# ic-tester.net
KiCad netlist of a schematic drawn in EAGLE
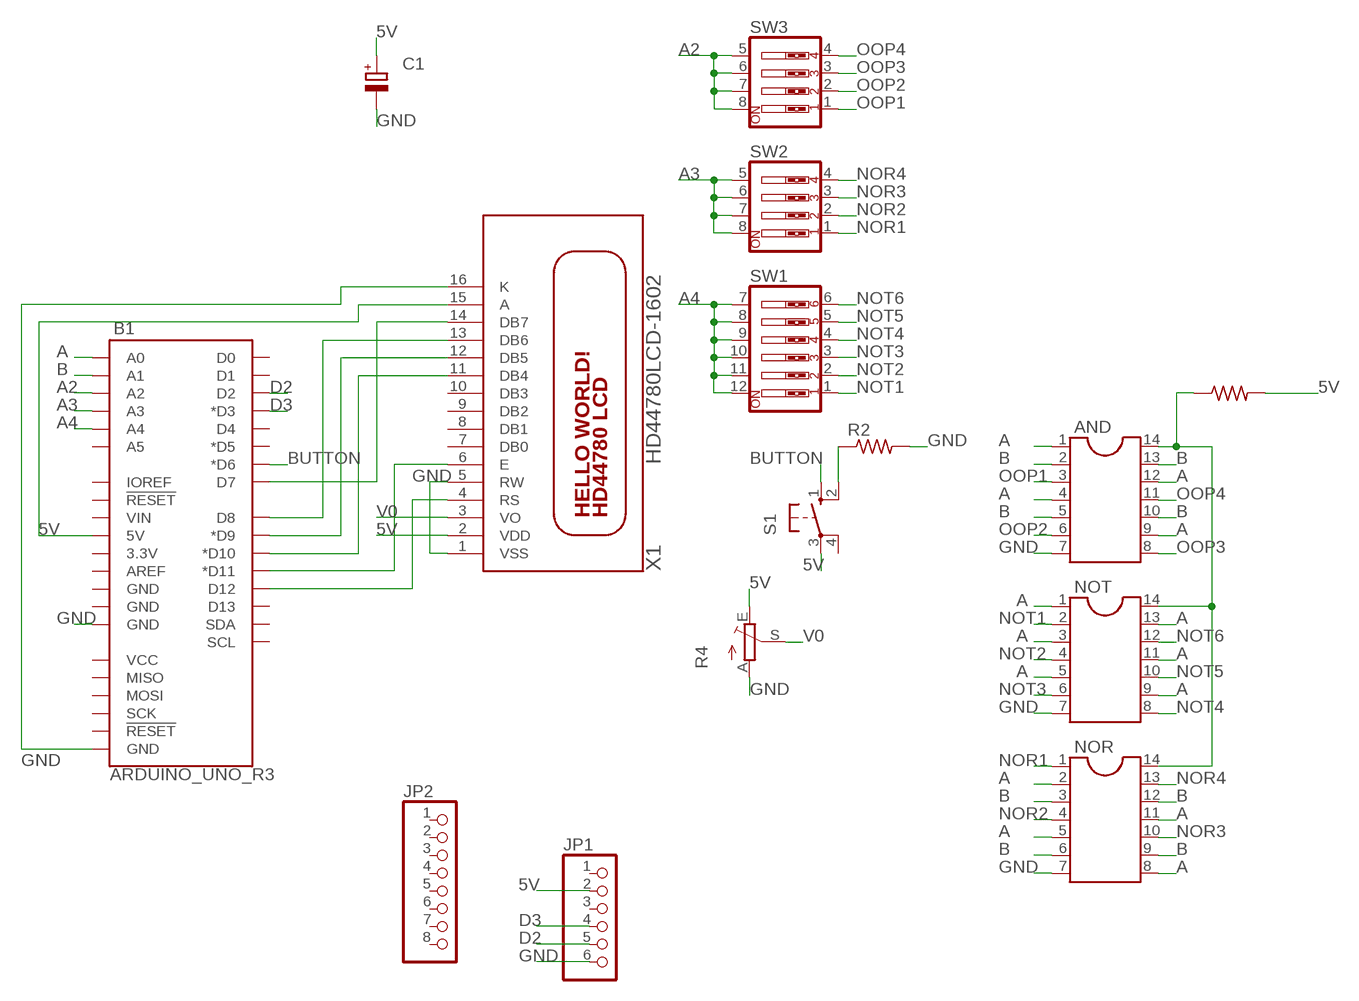
[diagram p0: schematic, sheet 1]

(export (version "E")
  (design (tool "Eeschema 10.0.6"))
  (components
    (comp (ref "AND")
      (value "DIL14")
      (footprint "eagle-import:DIL14")
      (libsource (lib "eagle-import") (part "DIL14"))
    )
    (comp (ref "B1")
      (value "ARDUINO_UNO_R3")
      (footprint "eagle-import:ARDUINO_R3")
      (libsource (lib "eagle-import") (part "ARDUINO_UNO_R3"))
    )
    (comp (ref "C1")
      (value "CPOL-EUE7.5-16")
      (footprint "eagle-import:E7,5-16")
      (libsource (lib "eagle-import") (part "CPOL-EUE7.5-16"))
    )
    (comp (ref "JP1")
      (value "PINHD-1X6")
      (footprint "eagle-import:1X06")
      (libsource (lib "eagle-import") (part "PINHD-1X6"))
    )
    (comp (ref "JP2")
      (value "PINHD-1X8BIG")
      (footprint "eagle-import:1X08-BIG")
      (libsource (lib "eagle-import") (part "PINHD-1X8BIG"))
    )
    (comp (ref "NOR")
      (value "DIL14")
      (footprint "eagle-import:DIL14")
      (libsource (lib "eagle-import") (part "DIL14"))
    )
    (comp (ref "NOT")
      (value "DIL14")
      (footprint "eagle-import:DIL14")
      (libsource (lib "eagle-import") (part "DIL14"))
    )
    (comp (ref "R1")
      (value "R-US_0204/7")
      (footprint "eagle-import:0204_7")
      (libsource (lib "eagle-import") (part "R-US_0204/7"))
    )
    (comp (ref "R2")
      (value "R-US_0204/7")
      (footprint "eagle-import:0204_7")
      (libsource (lib "eagle-import") (part "R-US_0204/7"))
    )
    (comp (ref "R4")
      (value "TRIM_EU-LI10")
      (footprint "eagle-import:LI10")
      (libsource (lib "eagle-import") (part "TRIM_EU-LI10"))
    )
    (comp (ref "S1")
      (value "10-XX")
      (footprint "eagle-import:B3F-10XX")
      (fields (field (name "MPN") "B3F-1000"))
      (libsource (lib "eagle-import") (part "10-XX"))
    )
    (comp (ref "SW1")
      (value "SW_DIP-6")
      (footprint "eagle-import:EDG-06")
      (libsource (lib "eagle-import") (part "SW_DIP-6"))
    )
    (comp (ref "SW2")
      (value "SW_DIP-4")
      (footprint "eagle-import:EDG-04")
      (libsource (lib "eagle-import") (part "SW_DIP-4"))
    )
    (comp (ref "SW3")
      (value "SW_DIP-4")
      (footprint "eagle-import:EDG-04")
      (libsource (lib "eagle-import") (part "SW_DIP-4"))
    )
    (comp (ref "X1")
      (value "HD44780LCD-1602")
      (footprint "eagle-import:LCD1602")
      (libsource (lib "eagle-import") (part "HD44780LCD-1602"))
    )
  )
  (nets
    (net (code "1") (name "/5V") (class "Default")
      (node (ref "B1") (pin "5V") (pinfunction "5V_5V") (pintype "bidirectional"))
      (node (ref "C1") (pin "+") (pinfunction "+_+") (pintype "passive"))
      (node (ref "JP1") (pin "2") (pinfunction "2_2") (pintype "passive"))
      (node (ref "R1") (pin "2") (pinfunction "2_2") (pintype "passive"))
      (node (ref "R4") (pin "E") (pinfunction "E_E") (pintype "passive"))
      (node (ref "S1") (pin "3") (pinfunction "P_3") (pintype "passive"))
      (node (ref "X1") (pin "15") (pinfunction "A_15") (pintype "input"))
      (node (ref "X1") (pin "2") (pinfunction "VDD_2") (pintype "power_in"))
    )
    (net (code "2") (name "/A") (class "Default")
      (node (ref "AND") (pin "1") (pinfunction "1_1") (pintype "passive"))
      (node (ref "AND") (pin "12") (pinfunction "12_12") (pintype "passive"))
      (node (ref "AND") (pin "4") (pinfunction "4_4") (pintype "passive"))
      (node (ref "AND") (pin "9") (pinfunction "9_9") (pintype "passive"))
      (node (ref "B1") (pin "A0") (pinfunction "A0_A0") (pintype "bidirectional"))
      (node (ref "NOR") (pin "11") (pinfunction "11_11") (pintype "passive"))
      (node (ref "NOR") (pin "2") (pinfunction "2_2") (pintype "passive"))
      (node (ref "NOR") (pin "5") (pinfunction "5_5") (pintype "passive"))
      (node (ref "NOR") (pin "8") (pinfunction "8_8") (pintype "passive"))
      (node (ref "NOT") (pin "1") (pinfunction "1_1") (pintype "passive"))
      (node (ref "NOT") (pin "11") (pinfunction "11_11") (pintype "passive"))
      (node (ref "NOT") (pin "13") (pinfunction "13_13") (pintype "passive"))
      (node (ref "NOT") (pin "3") (pinfunction "3_3") (pintype "passive"))
      (node (ref "NOT") (pin "5") (pinfunction "5_5") (pintype "passive"))
      (node (ref "NOT") (pin "9") (pinfunction "9_9") (pintype "passive"))
    )
    (net (code "3") (name "/A2") (class "Default")
      (node (ref "B1") (pin "A2") (pinfunction "A2_A2") (pintype "bidirectional"))
      (node (ref "SW3") (pin "5") (pinfunction "5_5") (pintype "passive"))
      (node (ref "SW3") (pin "6") (pinfunction "6_6") (pintype "passive"))
      (node (ref "SW3") (pin "7") (pinfunction "7_7") (pintype "passive"))
      (node (ref "SW3") (pin "8") (pinfunction "8_8") (pintype "passive"))
    )
    (net (code "4") (name "/A3") (class "Default")
      (node (ref "B1") (pin "A3") (pinfunction "A3_A3") (pintype "bidirectional"))
      (node (ref "SW2") (pin "5") (pinfunction "5_5") (pintype "passive"))
      (node (ref "SW2") (pin "6") (pinfunction "6_6") (pintype "passive"))
      (node (ref "SW2") (pin "7") (pinfunction "7_7") (pintype "passive"))
      (node (ref "SW2") (pin "8") (pinfunction "8_8") (pintype "passive"))
    )
    (net (code "5") (name "/A4") (class "Default")
      (node (ref "B1") (pin "A4") (pinfunction "A4_A4") (pintype "bidirectional"))
      (node (ref "SW1") (pin "10") (pinfunction "10_10") (pintype "passive"))
      (node (ref "SW1") (pin "11") (pinfunction "11_11") (pintype "passive"))
      (node (ref "SW1") (pin "12") (pinfunction "12_12") (pintype "passive"))
      (node (ref "SW1") (pin "7") (pinfunction "7_7") (pintype "passive"))
      (node (ref "SW1") (pin "8") (pinfunction "8_8") (pintype "passive"))
      (node (ref "SW1") (pin "9") (pinfunction "9_9") (pintype "passive"))
    )
    (net (code "6") (name "/B") (class "Default")
      (node (ref "AND") (pin "10") (pinfunction "10_10") (pintype "passive"))
      (node (ref "AND") (pin "13") (pinfunction "13_13") (pintype "passive"))
      (node (ref "AND") (pin "2") (pinfunction "2_2") (pintype "passive"))
      (node (ref "AND") (pin "5") (pinfunction "5_5") (pintype "passive"))
      (node (ref "B1") (pin "A1") (pinfunction "A1_A1") (pintype "bidirectional"))
      (node (ref "NOR") (pin "12") (pinfunction "12_12") (pintype "passive"))
      (node (ref "NOR") (pin "3") (pinfunction "3_3") (pintype "passive"))
      (node (ref "NOR") (pin "6") (pinfunction "6_6") (pintype "passive"))
      (node (ref "NOR") (pin "9") (pinfunction "9_9") (pintype "passive"))
    )
    (net (code "7") (name "/BUTTON") (class "Default")
      (node (ref "B1") (pin "D6") (pinfunction "*D6_D6") (pintype "bidirectional"))
      (node (ref "S1") (pin "1") (pinfunction "S_1") (pintype "passive"))
    )
    (net (code "8") (name "/D2") (class "Default")
      (node (ref "B1") (pin "D2") (pinfunction "D2_D2") (pintype "bidirectional"))
      (node (ref "JP1") (pin "5") (pinfunction "5_5") (pintype "passive"))
    )
    (net (code "9") (name "/D3") (class "Default")
      (node (ref "B1") (pin "D3") (pinfunction "*D3_D3") (pintype "bidirectional"))
      (node (ref "JP1") (pin "4") (pinfunction "4_4") (pintype "passive"))
    )
    (net (code "10") (name "/GND") (class "Default")
      (node (ref "AND") (pin "7") (pinfunction "7_7") (pintype "passive"))
      (node (ref "B1") (pin "GND@1") (pinfunction "GND_GND@1") (pintype "bidirectional"))
      (node (ref "B1") (pin "GND@2") (pinfunction "GND_GND@2") (pintype "bidirectional"))
      (node (ref "C1") (pin "-") (pinfunction "-_-") (pintype "passive"))
      (node (ref "JP1") (pin "6") (pinfunction "6_6") (pintype "passive"))
      (node (ref "NOR") (pin "7") (pinfunction "7_7") (pintype "passive"))
      (node (ref "NOT") (pin "7") (pinfunction "7_7") (pintype "passive"))
      (node (ref "R2") (pin "2") (pinfunction "2_2") (pintype "passive"))
      (node (ref "R4") (pin "A") (pinfunction "A_A") (pintype "passive"))
      (node (ref "X1") (pin "1") (pinfunction "VSS_1") (pintype "power_in"))
      (node (ref "X1") (pin "16") (pinfunction "K_16") (pintype "input"))
      (node (ref "X1") (pin "5") (pinfunction "RW_5") (pintype "input"))
    )
    (net (code "11") (name "/NOR1") (class "Default")
      (node (ref "NOR") (pin "1") (pinfunction "1_1") (pintype "passive"))
      (node (ref "SW2") (pin "1") (pinfunction "1_1") (pintype "passive"))
    )
    (net (code "12") (name "/NOR2") (class "Default")
      (node (ref "NOR") (pin "4") (pinfunction "4_4") (pintype "passive"))
      (node (ref "SW2") (pin "2") (pinfunction "2_2") (pintype "passive"))
    )
    (net (code "13") (name "/NOR3") (class "Default")
      (node (ref "NOR") (pin "10") (pinfunction "10_10") (pintype "passive"))
      (node (ref "SW2") (pin "3") (pinfunction "3_3") (pintype "passive"))
    )
    (net (code "14") (name "/NOR4") (class "Default")
      (node (ref "NOR") (pin "13") (pinfunction "13_13") (pintype "passive"))
      (node (ref "SW2") (pin "4") (pinfunction "4_4") (pintype "passive"))
    )
    (net (code "15") (name "/NOT1") (class "Default")
      (node (ref "NOT") (pin "2") (pinfunction "2_2") (pintype "passive"))
      (node (ref "SW1") (pin "1") (pinfunction "1_1") (pintype "passive"))
    )
    (net (code "16") (name "/NOT2") (class "Default")
      (node (ref "NOT") (pin "4") (pinfunction "4_4") (pintype "passive"))
      (node (ref "SW1") (pin "2") (pinfunction "2_2") (pintype "passive"))
    )
    (net (code "17") (name "/NOT3") (class "Default")
      (node (ref "NOT") (pin "6") (pinfunction "6_6") (pintype "passive"))
      (node (ref "SW1") (pin "3") (pinfunction "3_3") (pintype "passive"))
    )
    (net (code "18") (name "/NOT4") (class "Default")
      (node (ref "NOT") (pin "8") (pinfunction "8_8") (pintype "passive"))
      (node (ref "SW1") (pin "4") (pinfunction "4_4") (pintype "passive"))
    )
    (net (code "19") (name "/NOT5") (class "Default")
      (node (ref "NOT") (pin "10") (pinfunction "10_10") (pintype "passive"))
      (node (ref "SW1") (pin "5") (pinfunction "5_5") (pintype "passive"))
    )
    (net (code "20") (name "/NOT6") (class "Default")
      (node (ref "NOT") (pin "12") (pinfunction "12_12") (pintype "passive"))
      (node (ref "SW1") (pin "6") (pinfunction "6_6") (pintype "passive"))
    )
    (net (code "21") (name "/OOP1") (class "Default")
      (node (ref "AND") (pin "3") (pinfunction "3_3") (pintype "passive"))
      (node (ref "SW3") (pin "1") (pinfunction "1_1") (pintype "passive"))
    )
    (net (code "22") (name "/OOP2") (class "Default")
      (node (ref "AND") (pin "6") (pinfunction "6_6") (pintype "passive"))
      (node (ref "SW3") (pin "2") (pinfunction "2_2") (pintype "passive"))
    )
    (net (code "23") (name "/OOP3") (class "Default")
      (node (ref "AND") (pin "8") (pinfunction "8_8") (pintype "passive"))
      (node (ref "SW3") (pin "3") (pinfunction "3_3") (pintype "passive"))
    )
    (net (code "24") (name "/OOP4") (class "Default")
      (node (ref "AND") (pin "11") (pinfunction "11_11") (pintype "passive"))
      (node (ref "SW3") (pin "4") (pinfunction "4_4") (pintype "passive"))
    )
    (net (code "25") (name "/V0") (class "Default")
      (node (ref "R4") (pin "S") (pinfunction "S_S") (pintype "passive"))
      (node (ref "X1") (pin "3") (pinfunction "VO_3") (pintype "input"))
    )
    (net (code "26") (name "Net-(AND-Pad14)") (class "Default")
      (node (ref "AND") (pin "14") (pinfunction "14_14") (pintype "passive"))
      (node (ref "NOR") (pin "14") (pinfunction "14_14") (pintype "passive"))
      (node (ref "NOT") (pin "14") (pinfunction "14_14") (pintype "passive"))
      (node (ref "R1") (pin "1") (pinfunction "1_1") (pintype "passive"))
    )
    (net (code "27") (name "Net-(B1-*D9)") (class "Default")
      (node (ref "B1") (pin "D9") (pinfunction "*D9_D9") (pintype "bidirectional"))
      (node (ref "X1") (pin "12") (pinfunction "DB5_12") (pintype "bidirectional"))
    )
    (net (code "28") (name "Net-(B1-*D10)") (class "Default")
      (node (ref "B1") (pin "D10") (pinfunction "*D10_D10") (pintype "bidirectional"))
      (node (ref "X1") (pin "11") (pinfunction "DB4_11") (pintype "bidirectional"))
    )
    (net (code "29") (name "Net-(B1-*D11)") (class "Default")
      (node (ref "B1") (pin "D11") (pinfunction "*D11_D11") (pintype "bidirectional"))
      (node (ref "X1") (pin "6") (pinfunction "E_6") (pintype "input"))
    )
    (net (code "30") (name "Net-(S1-S1)") (class "Default")
      (node (ref "R2") (pin "1") (pinfunction "1_1") (pintype "passive"))
      (node (ref "S1") (pin "2") (pinfunction "S1_2") (pintype "passive"))
    )
    (net (code "31") (name "Net-(X1-DB6)") (class "Default")
      (node (ref "B1") (pin "D8") (pinfunction "D8_D8") (pintype "bidirectional"))
      (node (ref "X1") (pin "13") (pinfunction "DB6_13") (pintype "bidirectional"))
    )
    (net (code "32") (name "Net-(X1-DB7)") (class "Default")
      (node (ref "B1") (pin "D7") (pinfunction "D7_D7") (pintype "bidirectional"))
      (node (ref "X1") (pin "14") (pinfunction "DB7_14") (pintype "bidirectional"))
    )
    (net (code "33") (name "Net-(X1-RS)") (class "Default")
      (node (ref "B1") (pin "D12") (pinfunction "D12_D12") (pintype "bidirectional"))
      (node (ref "X1") (pin "4") (pinfunction "RS_4") (pintype "input"))
    )
    (net (code "34") (name "unconnected-(B1-*D5-PadD5)") (class "Default")
      (node (ref "B1") (pin "D5") (pinfunction "*D5_D5") (pintype "bidirectional"))
    )
    (net (code "35") (name "unconnected-(B1-GND-PadGND@3)") (class "Default")
      (node (ref "B1") (pin "GND@3") (pinfunction "GND_GND@3") (pintype "bidirectional"))
    )
    (net (code "36") (name "unconnected-(B1-GND-PadGND@4)") (class "Default")
      (node (ref "B1") (pin "GND@4") (pinfunction "GND_GND@4") (pintype "bidirectional"))
    )
    (net (code "37") (name "unconnected-(B1-Pad3.3V)") (class "Default")
      (node (ref "B1") (pin "3.3V") (pinfunction "3.3V_3.3V") (pintype "bidirectional"))
    )
    (net (code "38") (name "unconnected-(B1-PadA5)") (class "Default")
      (node (ref "B1") (pin "A5") (pinfunction "A5_A5") (pintype "bidirectional"))
    )
    (net (code "39") (name "unconnected-(B1-PadAREF)") (class "Default")
      (node (ref "B1") (pin "AREF") (pinfunction "AREF_AREF") (pintype "bidirectional"))
    )
    (net (code "40") (name "unconnected-(B1-PadD0)") (class "Default")
      (node (ref "B1") (pin "D0") (pinfunction "D0_D0") (pintype "bidirectional"))
    )
    (net (code "41") (name "unconnected-(B1-PadD1)") (class "Default")
      (node (ref "B1") (pin "D1") (pinfunction "D1_D1") (pintype "bidirectional"))
    )
    (net (code "42") (name "unconnected-(B1-PadD4)") (class "Default")
      (node (ref "B1") (pin "D4") (pinfunction "D4_D4") (pintype "bidirectional"))
    )
    (net (code "43") (name "unconnected-(B1-PadD13)") (class "Default")
      (node (ref "B1") (pin "D13") (pinfunction "D13_D13") (pintype "bidirectional"))
    )
    (net (code "44") (name "unconnected-(B1-PadIOREF)") (class "Default")
      (node (ref "B1") (pin "IOREF") (pinfunction "IOREF_IOREF") (pintype "bidirectional"))
    )
    (net (code "45") (name "unconnected-(B1-PadMISO)") (class "Default")
      (node (ref "B1") (pin "MISO") (pinfunction "MISO_MISO") (pintype "bidirectional"))
    )
    (net (code "46") (name "unconnected-(B1-PadMOSI)") (class "Default")
      (node (ref "B1") (pin "MOSI") (pinfunction "MOSI_MOSI") (pintype "bidirectional"))
    )
    (net (code "47") (name "unconnected-(B1-PadSCK)") (class "Default")
      (node (ref "B1") (pin "SCK") (pinfunction "SCK_SCK") (pintype "bidirectional"))
    )
    (net (code "48") (name "unconnected-(B1-PadSCL)") (class "Default")
      (node (ref "B1") (pin "SCL") (pinfunction "SCL_SCL") (pintype "bidirectional"))
    )
    (net (code "49") (name "unconnected-(B1-PadSDA)") (class "Default")
      (node (ref "B1") (pin "SDA") (pinfunction "SDA_SDA") (pintype "bidirectional"))
    )
    (net (code "50") (name "unconnected-(B1-PadVCC)") (class "Default")
      (node (ref "B1") (pin "VCC") (pinfunction "VCC_VCC") (pintype "bidirectional"))
    )
    (net (code "51") (name "unconnected-(B1-PadVIN)") (class "Default")
      (node (ref "B1") (pin "VIN") (pinfunction "VIN_VIN") (pintype "bidirectional"))
    )
    (net (code "52") (name "unconnected-(B1-~{RESET}-PadRESET@1)") (class "Default")
      (node (ref "B1") (pin "RESET@1") (pinfunction "~{RESET}_RESET@1") (pintype "bidirectional"))
    )
    (net (code "53") (name "unconnected-(B1-~{RESET}-PadRESET@2)") (class "Default")
      (node (ref "B1") (pin "RESET@2") (pinfunction "~{RESET}_RESET@2") (pintype "bidirectional"))
    )
    (net (code "54") (name "unconnected-(JP1-Pad1)") (class "Default")
      (node (ref "JP1") (pin "1") (pinfunction "1_1") (pintype "passive"))
    )
    (net (code "55") (name "unconnected-(JP1-Pad3)") (class "Default")
      (node (ref "JP1") (pin "3") (pinfunction "3_3") (pintype "passive"))
    )
    (net (code "56") (name "unconnected-(JP2-Pad1)") (class "Default")
      (node (ref "JP2") (pin "1") (pinfunction "1_1") (pintype "passive"))
    )
    (net (code "57") (name "unconnected-(JP2-Pad2)") (class "Default")
      (node (ref "JP2") (pin "2") (pinfunction "2_2") (pintype "passive"))
    )
    (net (code "58") (name "unconnected-(JP2-Pad3)") (class "Default")
      (node (ref "JP2") (pin "3") (pinfunction "3_3") (pintype "passive"))
    )
    (net (code "59") (name "unconnected-(JP2-Pad4)") (class "Default")
      (node (ref "JP2") (pin "4") (pinfunction "4_4") (pintype "passive"))
    )
    (net (code "60") (name "unconnected-(JP2-Pad5)") (class "Default")
      (node (ref "JP2") (pin "5") (pinfunction "5_5") (pintype "passive"))
    )
    (net (code "61") (name "unconnected-(JP2-Pad6)") (class "Default")
      (node (ref "JP2") (pin "6") (pinfunction "6_6") (pintype "passive"))
    )
    (net (code "62") (name "unconnected-(JP2-Pad7)") (class "Default")
      (node (ref "JP2") (pin "7") (pinfunction "7_7") (pintype "passive"))
    )
    (net (code "63") (name "unconnected-(JP2-Pad8)") (class "Default")
      (node (ref "JP2") (pin "8") (pinfunction "8_8") (pintype "passive"))
    )
    (net (code "64") (name "unconnected-(S1-P1-Pad4)") (class "Default")
      (node (ref "S1") (pin "4") (pinfunction "P1_4") (pintype "passive"))
    )
    (net (code "65") (name "unconnected-(X1-DB0-Pad7)") (class "Default")
      (node (ref "X1") (pin "7") (pinfunction "DB0_7") (pintype "bidirectional"))
    )
    (net (code "66") (name "unconnected-(X1-DB1-Pad8)") (class "Default")
      (node (ref "X1") (pin "8") (pinfunction "DB1_8") (pintype "bidirectional"))
    )
    (net (code "67") (name "unconnected-(X1-DB2-Pad9)") (class "Default")
      (node (ref "X1") (pin "9") (pinfunction "DB2_9") (pintype "bidirectional"))
    )
    (net (code "68") (name "unconnected-(X1-DB3-Pad10)") (class "Default")
      (node (ref "X1") (pin "10") (pinfunction "DB3_10") (pintype "bidirectional"))
    )
  )
)
